# Main_heet.net
KiCad netlist of a schematic drawn in Altium Designer
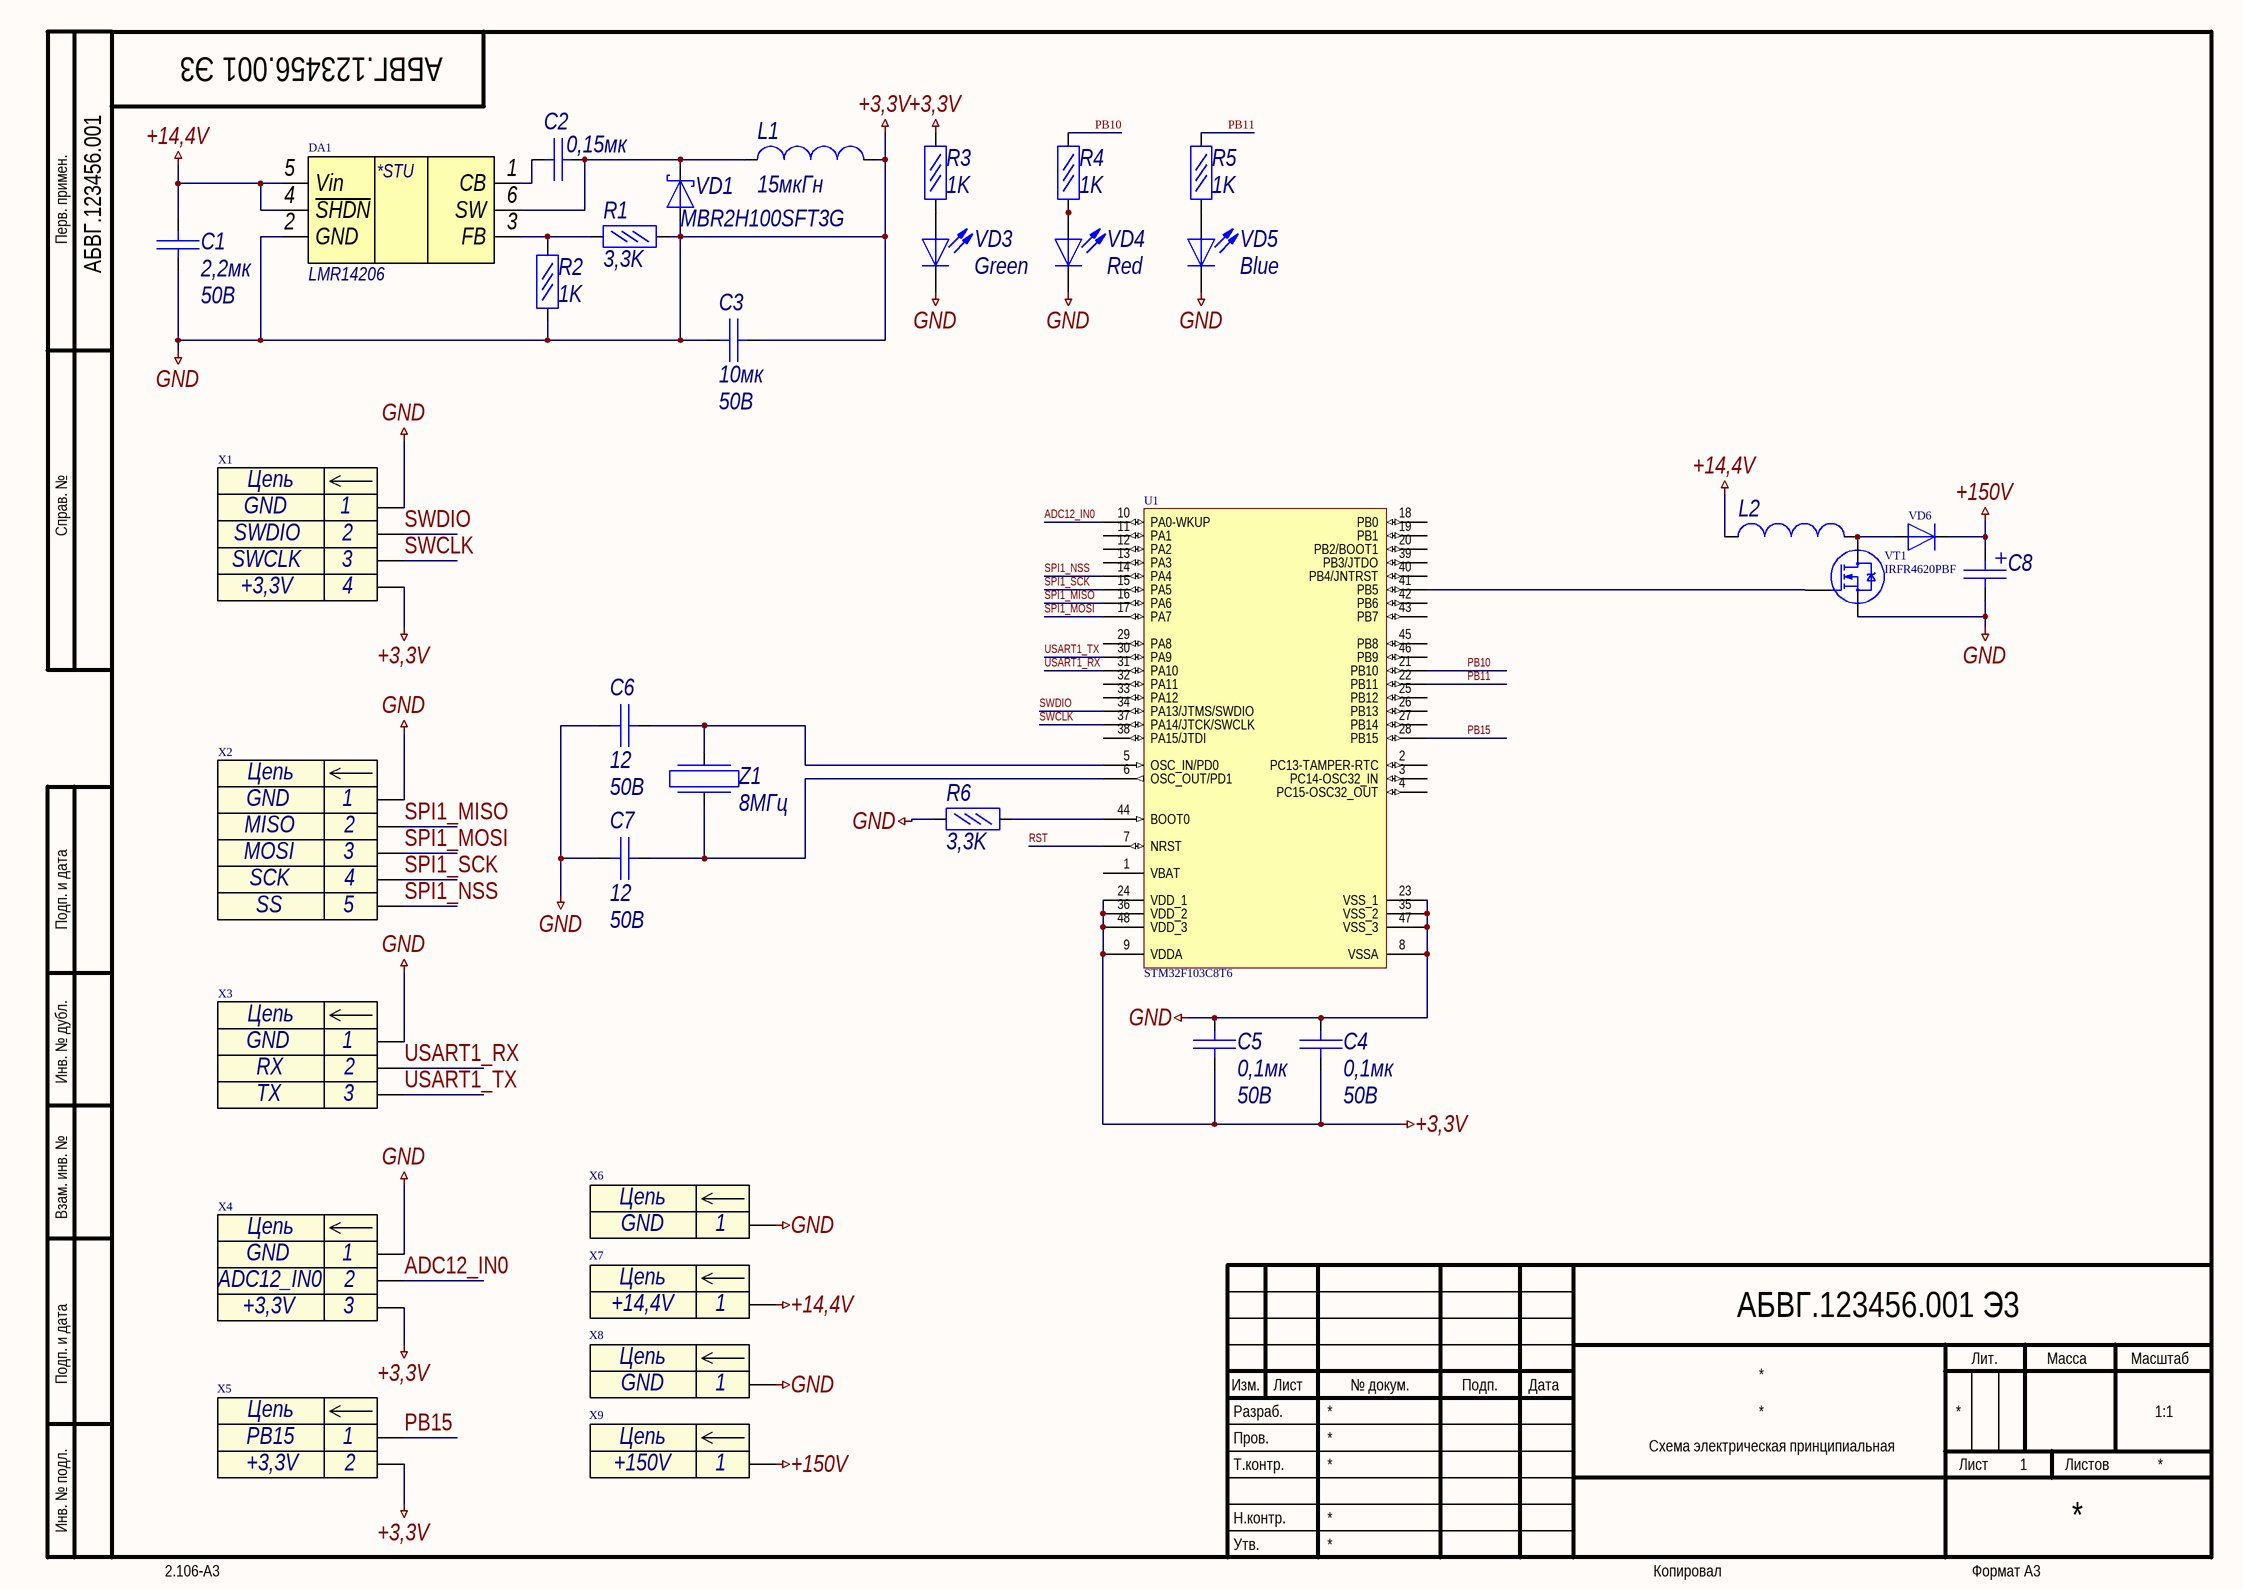
[diagram p0: Main heet.SchDoc]

(export (version "E")
  (design (tool "Eeschema 10.0.6"))
  (components
    (comp (ref "C1")
      (value "2,2мк")
      (footprint "libPCB:NPC0805")
      (description "Конденсатор кер.")
      (fields (field (name "MANUFACTURER") "Yageo") (field (name "VOLTAGE") "50В"))
      (libsource (lib "libSCH") (part "Capacitor ceramic"))
    )
    (comp (ref "C2")
      (value "0,15мк")
      (footprint "libPCB:NPC0805")
      (description "Конденсатор кер.")
      (fields (field (name "MANUFACTURER") "Yageo"))
      (libsource (lib "libSCH") (part "Capacitor ceramic"))
    )
    (comp (ref "C3")
      (value "10мк")
      (footprint "libPCB:NPC0805")
      (description "Конденсатор кер.")
      (fields (field (name "MANUFACTURER") "Yageo") (field (name "VOLTAGE") "50В"))
      (libsource (lib "libSCH") (part "Capacitor ceramic"))
    )
    (comp (ref "C4")
      (value "0,1мк")
      (footprint "libPCB:NPC0805")
      (description "Конденсатор кер.")
      (fields (field (name "MANUFACTURER") "Yageo") (field (name "VOLTAGE") "50В"))
      (libsource (lib "libSCH") (part "Capacitor ceramic"))
    )
    (comp (ref "C5")
      (value "0,1мк")
      (footprint "libPCB:NPC0805")
      (description "Конденсатор кер.")
      (fields (field (name "MANUFACTURER") "Yageo") (field (name "VOLTAGE") "50В"))
      (libsource (lib "libSCH") (part "Capacitor ceramic"))
    )
    (comp (ref "C6")
      (value "12")
      (footprint "libPCB:NPC0805")
      (description "Конденсатор кер.")
      (fields (field (name "MANUFACTURER") "Yageo") (field (name "VOLTAGE") "50В"))
      (libsource (lib "libSCH") (part "Capacitor ceramic"))
    )
    (comp (ref "C7")
      (value "12")
      (footprint "libPCB:NPC0805")
      (description "Конденсатор кер.")
      (fields (field (name "MANUFACTURER") "Yageo") (field (name "VOLTAGE") "50В"))
      (libsource (lib "libSCH") (part "Capacitor ceramic"))
    )
    (comp (ref "C8")
      (value "~")
      (footprint "LibPCB:CAP_PIN_RAD_D16_A7.5")
      (description "Конденсатор пол.")
      (libsource (lib "LibSCH") (part "Capacitor electrolytic"))
    )
    (comp (ref "DA1")
      (value "LMR14206")
      (footprint "LibPCB:SOT23-6")
      (description "DC\\DC")
      (fields (field (name "NAME") "LMR14206"))
      (libsource (lib "LibSCH") (part "LMR14206"))
    )
    (comp (ref "L1")
      (value "15мкГн")
      (footprint "libPCB:IND: B82472G")
      (description "Катушка индуктивности")
      (fields (field (name "MANUFACTURER") "Epcos"))
      (libsource (lib "libSCH") (part "Inductor"))
    )
    (comp (ref "L2")
      (value "~")
      (footprint "LibPCB:IND: B82477G")
      (description "Катушка индуктивности")
      (libsource (lib "LibSCH") (part "Inductor"))
    )
    (comp (ref "R1")
      (value "3,3K")
      (footprint "libPCB:R0603")
      (description "Резистор 0,05Вт")
      (fields (field (name "MANUFACTURER") "Yageo"))
      (libsource (lib "") (part "Резистор  0,05Вт_1"))
    )
    (comp (ref "R2")
      (value "1K")
      (footprint "libPCB:R0603")
      (description "Резистор 0,05Вт")
      (fields (field (name "MANUFACTURER") "Yageo"))
      (libsource (lib "libSCH") (part "Резистор  0,05Вт"))
    )
    (comp (ref "R3")
      (value "1K")
      (footprint "libPCB:R0603")
      (description "Резистор 0,05Вт")
      (fields (field (name "MANUFACTURER") "Yageo"))
      (libsource (lib "libSCH") (part "Резистор  0,05Вт"))
    )
    (comp (ref "R4")
      (value "1K")
      (footprint "libPCB:R0603")
      (description "Резистор 0,05Вт")
      (fields (field (name "MANUFACTURER") "Yageo"))
      (libsource (lib "libSCH") (part "Резистор  0,05Вт"))
    )
    (comp (ref "R5")
      (value "1K")
      (footprint "libPCB:R0603")
      (description "Резистор 0,05Вт")
      (fields (field (name "MANUFACTURER") "Yageo"))
      (libsource (lib "libSCH") (part "Резистор  0,05Вт"))
    )
    (comp (ref "R6")
      (value "3,3K")
      (footprint "libPCB:R0603")
      (description "Резистор 0,05Вт")
      (fields (field (name "MANUFACTURER") "Yageo"))
      (libsource (lib "") (part "Резистор  0,05Вт_1"))
    )
    (comp (ref "U1")
      (value "STM32F103C8T6")
      (footprint "LibPCB:LQFP48")
      (description "STM32 ARM-based 32-bit MCU with 64 Kbytes Flash, 48-pin LQFP, Industrial Temperature")
      (fields (field (name "PUBLISHER") "Altium Limited"))
      (libsource (lib "LibSCH") (part "STM32F103C8T6"))
    )
    (comp (ref "VD1")
      (value "MBR2H100SFT3G")
      (footprint "libPCB:SOD123")
      (description "Диод Шоттки")
      (fields (field (name "MANUFACTURER") "ON Semiconductor"))
      (libsource (lib "libSCH") (part "DiodeSchottky"))
    )
    (comp (ref "VD3")
      (value "Green")
      (footprint "LibPCB:0603_LED _GREEN")
      (description "Светодиод SMD")
      (fields (field (name "MANUFACTURER") "KGB"))
      (libsource (lib "LibSCH") (part "LED"))
    )
    (comp (ref "VD4")
      (value "Red")
      (footprint "LibPCB:0603_LED _RED")
      (description "Светодиод SMD")
      (fields (field (name "MANUFACTURER") "KGB"))
      (libsource (lib "LibSCH") (part "LED"))
    )
    (comp (ref "VD5")
      (value "Blue")
      (footprint "LibPCB:0603_LED_BLUE")
      (description "Светодиод SMD")
      (fields (field (name "MANUFACTURER") "KGB"))
      (libsource (lib "LibSCH") (part "LED"))
    )
    (comp (ref "VD6")
      (value "*")
      (footprint "LibPCB:DO-214AA")
      (description "Диод")
      (libsource (lib "LibSCH") (part "Diode"))
    )
    (comp (ref "VT1")
      (value "IRFR4620PBF")
      (footprint "LibPCB:DPAK")
      (description "N-канальный транзистор")
      (fields (field (name "MANUFACTURER") "International Rectifier"))
      (libsource (lib "LibSCH") (part "IRFR4620PBF"))
    )
    (comp (ref "X1")
      (value "~")
      (footprint "LibPCB:PLS-4")
      (description "Разъем - 4 конт. вилка")
      (libsource (lib "LibSCH") (part "Header_4_plg"))
    )
    (comp (ref "X2")
      (value "~")
      (footprint "LibPCB:PLS-5")
      (description "Разъем - 5 конт. вилка")
      (libsource (lib "LibSCH") (part "Header_5_plg"))
    )
    (comp (ref "X3")
      (value "~")
      (footprint "LibPCB:PLS-3")
      (description "Разъем - 3 конт. вилка")
      (libsource (lib "LibSCH") (part "Header_3_plg"))
    )
    (comp (ref "X4")
      (value "~")
      (footprint "LibPCB:PLS-3")
      (description "Разъем - 3 конт. вилка")
      (libsource (lib "LibSCH") (part "Header_3_plg"))
    )
    (comp (ref "X5")
      (value "~")
      (footprint "LibPCB:PLS-2")
      (description "Разъем - 2 конт. вилка")
      (libsource (lib "LibSCH") (part "Header_2_plg"))
    )
    (comp (ref "X6")
      (value "~")
      (footprint "LibPCB:Pad")
      (description "Разъем - 1 конт. вилка")
      (libsource (lib "LibSCH") (part "Header_1_plg"))
    )
    (comp (ref "X7")
      (value "~")
      (footprint "LibPCB:Pad")
      (description "Разъем - 1 конт. вилка")
      (libsource (lib "LibSCH") (part "Header_1_plg"))
    )
    (comp (ref "X8")
      (value "~")
      (footprint "LibPCB:Pad")
      (description "Разъем - 1 конт. вилка")
      (libsource (lib "LibSCH") (part "Header_1_plg"))
    )
    (comp (ref "X9")
      (value "~")
      (footprint "LibPCB:Pad")
      (description "Разъем - 1 конт. вилка")
      (libsource (lib "LibSCH") (part "Header_1_plg"))
    )
    (comp (ref "Z1")
      (value "8МГц")
      (footprint "libPCB:QUARTZ")
      (description "Кварцевый резонатор")
      (fields (field (name "MANUFACTURER") "Geyer Electronics") (field (name "TOLERANCE") "30ppm"))
      (libsource (lib "libSCH") (part "KX-7T 12.0"))
    )
  )
  (nets
    (net (code "1") (name "+3,3V") (class "Default")
      (node (ref "C1") (pin "2") (pinfunction "2_2") (pintype "passive"))
      (node (ref "C3") (pin "1") (pinfunction "1_1") (pintype "passive"))
      (node (ref "C3") (pin "2") (pinfunction "2_2") (pintype "passive"))
      (node (ref "C4") (pin "1") (pinfunction "1_1") (pintype "passive"))
      (node (ref "C4") (pin "2") (pinfunction "2_2") (pintype "passive"))
      (node (ref "C5") (pin "1") (pinfunction "1_1") (pintype "passive"))
      (node (ref "C5") (pin "2") (pinfunction "2_2") (pintype "passive"))
      (node (ref "C6") (pin "2") (pinfunction "2_2") (pintype "passive"))
      (node (ref "C7") (pin "2") (pinfunction "2_2") (pintype "passive"))
      (node (ref "C8") (pin "2") (pinfunction "2_2") (pintype "passive"))
      (node (ref "DA1") (pin "2") (pinfunction "GND_2") (pintype "passive"))
      (node (ref "L1") (pin "2") (pinfunction "2_2") (pintype "passive"))
      (node (ref "R1") (pin "1") (pinfunction "1_1") (pintype "passive"))
      (node (ref "R2") (pin "2") (pinfunction "2_2") (pintype "passive"))
      (node (ref "R3") (pin "1") (pinfunction "1_1") (pintype "passive"))
      (node (ref "R6") (pin "2") (pinfunction "2_2") (pintype "passive"))
      (node (ref "U1") (pin "23") (pinfunction "VSS_1_23") (pintype "power_in"))
      (node (ref "U1") (pin "24") (pinfunction "VDD_1_24") (pintype "power_in"))
      (node (ref "U1") (pin "35") (pinfunction "VSS_2_35") (pintype "power_in"))
      (node (ref "U1") (pin "36") (pinfunction "VDD_2_36") (pintype "power_in"))
      (node (ref "U1") (pin "47") (pinfunction "VSS_3_47") (pintype "power_in"))
      (node (ref "U1") (pin "48") (pinfunction "VDD_3_48") (pintype "power_in"))
      (node (ref "U1") (pin "8") (pinfunction "VSSA_8") (pintype "power_in"))
      (node (ref "U1") (pin "9") (pinfunction "VDDA_9") (pintype "power_in"))
      (node (ref "VD1") (pin "2") (pinfunction "A_2") (pintype "passive"))
      (node (ref "VD3") (pin "1") (pinfunction "K_1") (pintype "passive"))
      (node (ref "VD4") (pin "1") (pinfunction "K_1") (pintype "passive"))
      (node (ref "VD5") (pin "1") (pinfunction "K_1") (pintype "passive"))
      (node (ref "VT1") (pin "S") (pinfunction "S_S") (pintype "passive"))
      (node (ref "X1") (pin "1") (pinfunction "1_1") (pintype "passive"))
      (node (ref "X1") (pin "4") (pinfunction "4_4") (pintype "passive"))
      (node (ref "X2") (pin "1") (pinfunction "1_1") (pintype "passive"))
      (node (ref "X3") (pin "1") (pinfunction "1_1") (pintype "passive"))
      (node (ref "X4") (pin "1") (pinfunction "1_1") (pintype "passive"))
      (node (ref "X4") (pin "3") (pinfunction "3_3") (pintype "passive"))
      (node (ref "X5") (pin "2") (pinfunction "2_2") (pintype "passive"))
      (node (ref "X6") (pin "1") (pinfunction "1_1") (pintype "passive"))
      (node (ref "X8") (pin "1") (pinfunction "1_1") (pintype "passive"))
    )
    (net (code "2") (name "+14,4V") (class "Default")
      (node (ref "C1") (pin "1") (pinfunction "1_1") (pintype "passive"))
      (node (ref "DA1") (pin "4") (pinfunction "~{SHDN}_4") (pintype "passive"))
      (node (ref "DA1") (pin "5") (pinfunction "Vin_5") (pintype "passive"))
      (node (ref "L2") (pin "1") (pinfunction "1_1") (pintype "passive"))
      (node (ref "X7") (pin "1") (pinfunction "1_1") (pintype "passive"))
    )
    (net (code "3") (name "+150V") (class "Default")
      (node (ref "C8") (pin "1") (pinfunction "1_1") (pintype "passive"))
      (node (ref "VD6") (pin "1") (pinfunction "K_1") (pintype "passive"))
      (node (ref "X9") (pin "1") (pinfunction "1_1") (pintype "passive"))
    )
    (net (code "4") (name "/ADC12_IN0") (class "Default")
      (node (ref "U1") (pin "10") (pinfunction "PA0-WKUP_10") (pintype "bidirectional"))
      (node (ref "X4") (pin "2") (pinfunction "2_2") (pintype "passive"))
    )
    (net (code "5") (name "/PB10") (class "Default")
      (node (ref "R4") (pin "1") (pinfunction "1_1") (pintype "passive"))
      (node (ref "U1") (pin "21") (pinfunction "PB10_21") (pintype "bidirectional"))
    )
    (net (code "6") (name "/PB11") (class "Default")
      (node (ref "R5") (pin "1") (pinfunction "1_1") (pintype "passive"))
      (node (ref "U1") (pin "22") (pinfunction "PB11_22") (pintype "bidirectional"))
    )
    (net (code "7") (name "/PB15") (class "Default")
      (node (ref "U1") (pin "28") (pinfunction "PB15_28") (pintype "bidirectional"))
      (node (ref "X5") (pin "1") (pinfunction "1_1") (pintype "passive"))
    )
    (net (code "8") (name "/RST") (class "Default")
      (node (ref "U1") (pin "7") (pinfunction "NRST_7") (pintype "bidirectional"))
    )
    (net (code "9") (name "/SPI1_MISO") (class "Default")
      (node (ref "U1") (pin "16") (pinfunction "PA6_16") (pintype "bidirectional"))
      (node (ref "X2") (pin "2") (pinfunction "2_2") (pintype "passive"))
    )
    (net (code "10") (name "/SPI1_MOSI") (class "Default")
      (node (ref "U1") (pin "17") (pinfunction "PA7_17") (pintype "bidirectional"))
      (node (ref "X2") (pin "3") (pinfunction "3_3") (pintype "passive"))
    )
    (net (code "11") (name "/SPI1_NSS") (class "Default")
      (node (ref "U1") (pin "14") (pinfunction "PA4_14") (pintype "bidirectional"))
      (node (ref "X2") (pin "5") (pinfunction "5_5") (pintype "passive"))
    )
    (net (code "12") (name "/SPI1_SCK") (class "Default")
      (node (ref "U1") (pin "15") (pinfunction "PA5_15") (pintype "bidirectional"))
      (node (ref "X2") (pin "4") (pinfunction "4_4") (pintype "passive"))
    )
    (net (code "13") (name "/SWCLK") (class "Default")
      (node (ref "U1") (pin "37") (pinfunction "PA14/JTCK/SWCLK_37") (pintype "bidirectional"))
      (node (ref "X1") (pin "3") (pinfunction "3_3") (pintype "passive"))
    )
    (net (code "14") (name "/SWDIO") (class "Default")
      (node (ref "U1") (pin "34") (pinfunction "PA13/JTMS/SWDIO_34") (pintype "bidirectional"))
      (node (ref "X1") (pin "2") (pinfunction "2_2") (pintype "passive"))
    )
    (net (code "15") (name "/USART1_RX") (class "Default")
      (node (ref "U1") (pin "31") (pinfunction "PA10_31") (pintype "bidirectional"))
      (node (ref "X3") (pin "2") (pinfunction "2_2") (pintype "passive"))
    )
    (net (code "16") (name "/USART1_TX") (class "Default")
      (node (ref "U1") (pin "30") (pinfunction "PA9_30") (pintype "bidirectional"))
      (node (ref "X3") (pin "3") (pinfunction "3_3") (pintype "passive"))
    )
    (net (code "17") (name "Net-(DA1-CB)") (class "Default")
      (node (ref "C2") (pin "1") (pinfunction "1_1") (pintype "passive"))
      (node (ref "DA1") (pin "1") (pinfunction "CB_1") (pintype "passive"))
    )
    (net (code "18") (name "Net-(DA1-FB)") (class "Default")
      (node (ref "DA1") (pin "3") (pinfunction "FB_3") (pintype "passive"))
      (node (ref "R1") (pin "2") (pinfunction "2_2") (pintype "passive"))
      (node (ref "R2") (pin "1") (pinfunction "1_1") (pintype "passive"))
    )
    (net (code "19") (name "Net-(DA1-SW)") (class "Default")
      (node (ref "C2") (pin "2") (pinfunction "2_2") (pintype "passive"))
      (node (ref "DA1") (pin "6") (pinfunction "SW_6") (pintype "passive"))
      (node (ref "L1") (pin "1") (pinfunction "1_1") (pintype "passive"))
      (node (ref "VD1") (pin "1") (pinfunction "K_1") (pintype "passive"))
    )
    (net (code "20") (name "Net-(U1-BOOT0)") (class "Default")
      (node (ref "R6") (pin "1") (pinfunction "1_1") (pintype "passive"))
      (node (ref "U1") (pin "44") (pinfunction "BOOT0_44") (pintype "input"))
    )
    (net (code "21") (name "Net-(U1-OSC_IN{slash}PD0)") (class "Default")
      (node (ref "C6") (pin "1") (pinfunction "1_1") (pintype "passive"))
      (node (ref "U1") (pin "5") (pinfunction "OSC_IN/PD0_5") (pintype "input"))
      (node (ref "Z1") (pin "1") (pinfunction "1_1") (pintype "passive"))
    )
    (net (code "22") (name "Net-(U1-OSC_OUT{slash}PD1)") (class "Default")
      (node (ref "C7") (pin "1") (pinfunction "1_1") (pintype "passive"))
      (node (ref "U1") (pin "6") (pinfunction "OSC_OUT/PD1_6") (pintype "output"))
      (node (ref "Z1") (pin "2") (pinfunction "2_2") (pintype "passive"))
    )
    (net (code "23") (name "Net-(U1-PB5)") (class "Default")
      (node (ref "U1") (pin "41") (pinfunction "PB5_41") (pintype "bidirectional"))
      (node (ref "VT1") (pin "G") (pinfunction "G_G") (pintype "passive"))
    )
    (net (code "24") (name "Net-(VD3-A)") (class "Default")
      (node (ref "R3") (pin "2") (pinfunction "2_2") (pintype "passive"))
      (node (ref "VD3") (pin "2") (pinfunction "A_2") (pintype "passive"))
    )
    (net (code "25") (name "Net-(VD4-A)") (class "Default")
      (node (ref "R4") (pin "2") (pinfunction "2_2") (pintype "passive"))
      (node (ref "VD4") (pin "2") (pinfunction "A_2") (pintype "passive"))
    )
    (net (code "26") (name "Net-(VD5-A)") (class "Default")
      (node (ref "R5") (pin "2") (pinfunction "2_2") (pintype "passive"))
      (node (ref "VD5") (pin "2") (pinfunction "A_2") (pintype "passive"))
    )
    (net (code "27") (name "Net-(VD6-A)") (class "Default")
      (node (ref "L2") (pin "2") (pinfunction "2_2") (pintype "passive"))
      (node (ref "VD6") (pin "2") (pinfunction "A_2") (pintype "passive"))
      (node (ref "VT1") (pin "D") (pinfunction "D_D") (pintype "passive"))
    )
    (net (code "28") (name "unconnected-(U1-PA1-Pad11)") (class "Default")
      (node (ref "U1") (pin "11") (pinfunction "PA1_11") (pintype "bidirectional"))
    )
    (net (code "29") (name "unconnected-(U1-PA2-Pad12)") (class "Default")
      (node (ref "U1") (pin "12") (pinfunction "PA2_12") (pintype "bidirectional"))
    )
    (net (code "30") (name "unconnected-(U1-PA3-Pad13)") (class "Default")
      (node (ref "U1") (pin "13") (pinfunction "PA3_13") (pintype "bidirectional"))
    )
    (net (code "31") (name "unconnected-(U1-PA8-Pad29)") (class "Default")
      (node (ref "U1") (pin "29") (pinfunction "PA8_29") (pintype "bidirectional"))
    )
    (net (code "32") (name "unconnected-(U1-PA11-Pad32)") (class "Default")
      (node (ref "U1") (pin "32") (pinfunction "PA11_32") (pintype "bidirectional"))
    )
    (net (code "33") (name "unconnected-(U1-PA12-Pad33)") (class "Default")
      (node (ref "U1") (pin "33") (pinfunction "PA12_33") (pintype "bidirectional"))
    )
    (net (code "34") (name "unconnected-(U1-PA15{slash}JTDI-Pad38)") (class "Default")
      (node (ref "U1") (pin "38") (pinfunction "PA15/JTDI_38") (pintype "bidirectional"))
    )
    (net (code "35") (name "unconnected-(U1-PB0-Pad18)") (class "Default")
      (node (ref "U1") (pin "18") (pinfunction "PB0_18") (pintype "bidirectional"))
    )
    (net (code "36") (name "unconnected-(U1-PB1-Pad19)") (class "Default")
      (node (ref "U1") (pin "19") (pinfunction "PB1_19") (pintype "bidirectional"))
    )
    (net (code "37") (name "unconnected-(U1-PB2{slash}BOOT1-Pad20)") (class "Default")
      (node (ref "U1") (pin "20") (pinfunction "PB2/BOOT1_20") (pintype "bidirectional"))
    )
    (net (code "38") (name "unconnected-(U1-PB3{slash}JTDO-Pad39)") (class "Default")
      (node (ref "U1") (pin "39") (pinfunction "PB3/JTDO_39") (pintype "bidirectional"))
    )
    (net (code "39") (name "unconnected-(U1-PB4{slash}JNTRST-Pad40)") (class "Default")
      (node (ref "U1") (pin "40") (pinfunction "PB4/JNTRST_40") (pintype "bidirectional"))
    )
    (net (code "40") (name "unconnected-(U1-PB6-Pad42)") (class "Default")
      (node (ref "U1") (pin "42") (pinfunction "PB6_42") (pintype "bidirectional"))
    )
    (net (code "41") (name "unconnected-(U1-PB7-Pad43)") (class "Default")
      (node (ref "U1") (pin "43") (pinfunction "PB7_43") (pintype "bidirectional"))
    )
    (net (code "42") (name "unconnected-(U1-PB8-Pad45)") (class "Default")
      (node (ref "U1") (pin "45") (pinfunction "PB8_45") (pintype "bidirectional"))
    )
    (net (code "43") (name "unconnected-(U1-PB9-Pad46)") (class "Default")
      (node (ref "U1") (pin "46") (pinfunction "PB9_46") (pintype "bidirectional"))
    )
    (net (code "44") (name "unconnected-(U1-PB12-Pad25)") (class "Default")
      (node (ref "U1") (pin "25") (pinfunction "PB12_25") (pintype "bidirectional"))
    )
    (net (code "45") (name "unconnected-(U1-PB13-Pad26)") (class "Default")
      (node (ref "U1") (pin "26") (pinfunction "PB13_26") (pintype "bidirectional"))
    )
    (net (code "46") (name "unconnected-(U1-PB14-Pad27)") (class "Default")
      (node (ref "U1") (pin "27") (pinfunction "PB14_27") (pintype "bidirectional"))
    )
    (net (code "47") (name "unconnected-(U1-PC13-TAMPER-RTC-Pad2)") (class "Default")
      (node (ref "U1") (pin "2") (pinfunction "PC13-TAMPER-RTC_2") (pintype "bidirectional"))
    )
    (net (code "48") (name "unconnected-(U1-PC14-OSC32_IN-Pad3)") (class "Default")
      (node (ref "U1") (pin "3") (pinfunction "PC14-OSC32_IN_3") (pintype "bidirectional"))
    )
    (net (code "49") (name "unconnected-(U1-PC15-OSC32_OUT-Pad4)") (class "Default")
      (node (ref "U1") (pin "4") (pinfunction "PC15-OSC32_OUT_4") (pintype "bidirectional"))
    )
    (net (code "50") (name "unconnected-(U1-VBAT-Pad1)") (class "Default")
      (node (ref "U1") (pin "1") (pinfunction "VBAT_1") (pintype "power_in"))
    )
  )
)
